# index.net
KiCad netlist of a schematic drawn in EAGLE
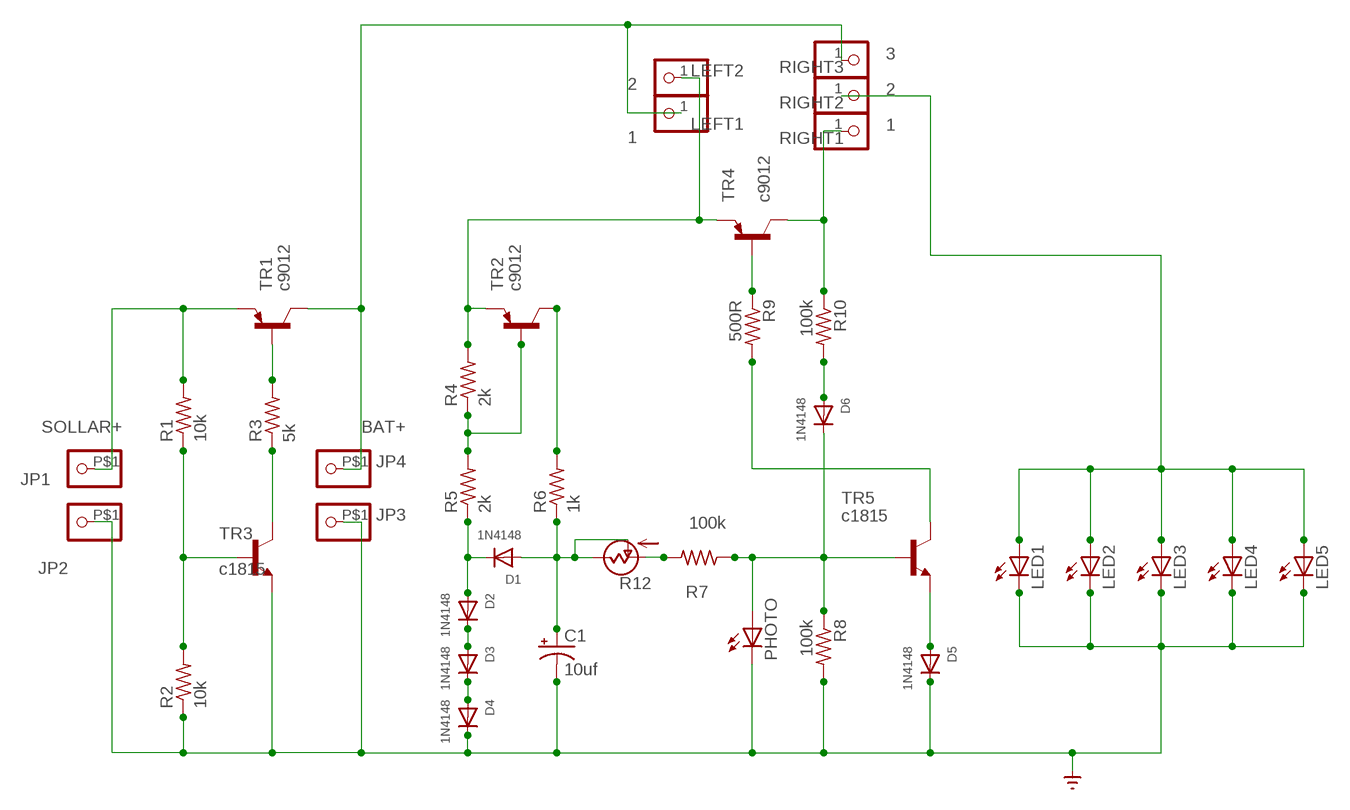
[diagram p0: schematic, sheet 1]

(export (version "E")
  (design (tool "Eeschema 10.0.6"))
  (components
    (comp (ref "C1")
      (value "10uf")
      (footprint "eagle-import:CPOL-RADIAL-10UF-25V")
      (libsource (lib "eagle-import") (part "CAP_POLPTH2"))
    )
    (comp (ref "D1")
      (value "1N4148")
      (footprint "eagle-import:DO-1N4148")
      (libsource (lib "eagle-import") (part "DIODEDO-1N4148"))
    )
    (comp (ref "D2")
      (value "1N4148")
      (footprint "eagle-import:DO-1N4148")
      (libsource (lib "eagle-import") (part "DIODEDO-1N4148"))
    )
    (comp (ref "D3")
      (value "1N4148")
      (footprint "eagle-import:DO-1N4148")
      (libsource (lib "eagle-import") (part "DIODEDO-1N4148"))
    )
    (comp (ref "D4")
      (value "1N4148")
      (footprint "eagle-import:DO-1N4148")
      (libsource (lib "eagle-import") (part "DIODEDO-1N4148"))
    )
    (comp (ref "D5")
      (value "1N4148")
      (footprint "eagle-import:DO-1N4148")
      (libsource (lib "eagle-import") (part "DIODEDO-1N4148"))
    )
    (comp (ref "D6")
      (value "1N4148")
      (footprint "eagle-import:DO-1N4148")
      (libsource (lib "eagle-import") (part "DIODEDO-1N4148"))
    )
    (comp (ref "JP1")
      (value "PINHD-1X1-BIGPOGO")
      (footprint "eagle-import:1X1-BIGPOGO")
      (libsource (lib "eagle-import") (part "PINHD-1X1-BIGPOGO"))
    )
    (comp (ref "JP2")
      (value "PINHD-1X1-BIGPOGO")
      (footprint "eagle-import:1X1-BIGPOGO")
      (libsource (lib "eagle-import") (part "PINHD-1X1-BIGPOGO"))
    )
    (comp (ref "JP3")
      (value "PINHD-1X1-BIGPOGO")
      (footprint "eagle-import:1X1-BIGPOGO")
      (libsource (lib "eagle-import") (part "PINHD-1X1-BIGPOGO"))
    )
    (comp (ref "JP4")
      (value "PINHD-1X1-BIGPOGO")
      (footprint "eagle-import:1X1-BIGPOGO")
      (libsource (lib "eagle-import") (part "PINHD-1X1-BIGPOGO"))
    )
    (comp (ref "LED1")
      (value "LED3MM")
      (footprint "eagle-import:LED3MM")
      (libsource (lib "eagle-import") (part "LED3MM"))
    )
    (comp (ref "LED2")
      (value "LED3MM")
      (footprint "eagle-import:LED3MM")
      (libsource (lib "eagle-import") (part "LED3MM"))
    )
    (comp (ref "LED3")
      (value "LED3MM")
      (footprint "eagle-import:LED3MM")
      (libsource (lib "eagle-import") (part "LED3MM"))
    )
    (comp (ref "LED4")
      (value "LED3MM")
      (footprint "eagle-import:LED3MM")
      (libsource (lib "eagle-import") (part "LED3MM"))
    )
    (comp (ref "LED5")
      (value "LED3MM")
      (footprint "eagle-import:LED3MM")
      (libsource (lib "eagle-import") (part "LED3MM"))
    )
    (comp (ref "LEFT1")
      (value "1")
      (footprint "eagle-import:1X01-CLEANBIG")
      (libsource (lib "eagle-import") (part "PINHD-1X1CB"))
    )
    (comp (ref "LEFT2")
      (value "2")
      (footprint "eagle-import:1X01-CLEANBIG")
      (libsource (lib "eagle-import") (part "PINHD-1X1CB"))
    )
    (comp (ref "PHOTO")
      (value "LED3MM")
      (footprint "eagle-import:LED3MM")
      (libsource (lib "eagle-import") (part "LED3MM"))
    )
    (comp (ref "R1")
      (value "10k")
      (footprint "eagle-import:0207_9")
      (libsource (lib "eagle-import") (part "R-US_0207/9"))
    )
    (comp (ref "R2")
      (value "10k")
      (footprint "eagle-import:0207_9")
      (libsource (lib "eagle-import") (part "R-US_0207/9"))
    )
    (comp (ref "R3")
      (value "5k")
      (footprint "eagle-import:0207_9")
      (libsource (lib "eagle-import") (part "R-US_0207/9"))
    )
    (comp (ref "R4")
      (value "2k")
      (footprint "eagle-import:0207_9")
      (libsource (lib "eagle-import") (part "R-US_0207/9"))
    )
    (comp (ref "R5")
      (value "2k")
      (footprint "eagle-import:0207_9")
      (libsource (lib "eagle-import") (part "R-US_0207/9"))
    )
    (comp (ref "R6")
      (value "1k")
      (footprint "eagle-import:0207_9")
      (libsource (lib "eagle-import") (part "R-US_0207/9"))
    )
    (comp (ref "R7")
      (value "100k")
      (footprint "eagle-import:0207_9")
      (libsource (lib "eagle-import") (part "R-US_0207/9"))
    )
    (comp (ref "R8")
      (value "100k")
      (footprint "eagle-import:0207_9")
      (libsource (lib "eagle-import") (part "R-US_0207/9"))
    )
    (comp (ref "R9")
      (value "500R")
      (footprint "eagle-import:0207_9")
      (libsource (lib "eagle-import") (part "R-US_0207/9"))
    )
    (comp (ref "R10")
      (value "100k")
      (footprint "eagle-import:0207_9")
      (libsource (lib "eagle-import") (part "R-US_0207/9"))
    )
    (comp (ref "R12")
      (value "POTTRECP10S")
      (footprint "eagle-import:ECP10S")
      (libsource (lib "eagle-import") (part "POTTRECP10S"))
    )
    (comp (ref "RIGHT1")
      (value "1")
      (footprint "eagle-import:1X01-CLEANBIG")
      (libsource (lib "eagle-import") (part "PINHD-1X1CB"))
    )
    (comp (ref "RIGHT2")
      (value "2")
      (footprint "eagle-import:1X01-CLEANBIG")
      (libsource (lib "eagle-import") (part "PINHD-1X1CB"))
    )
    (comp (ref "RIGHT3")
      (value "3")
      (footprint "eagle-import:1X01-CLEANBIG")
      (libsource (lib "eagle-import") (part "PINHD-1X1CB"))
    )
    (comp (ref "TR1")
      (value "c9012")
      (footprint "eagle-import:TO92-EBC-OVAL")
      (libsource (lib "eagle-import") (part "2N2907"))
    )
    (comp (ref "TR2")
      (value "c9012")
      (footprint "eagle-import:TO92-EBC-OVAL")
      (libsource (lib "eagle-import") (part "2N2907"))
    )
    (comp (ref "TR3")
      (value "c1815")
      (footprint "eagle-import:TO92-ECB")
      (libsource (lib "eagle-import") (part "-NPN-TO92-ECBBC639"))
    )
    (comp (ref "TR4")
      (value "c9012")
      (footprint "eagle-import:TO92-EBC-OVAL")
      (libsource (lib "eagle-import") (part "2N2907"))
    )
    (comp (ref "TR5")
      (value "c1815")
      (footprint "eagle-import:TO92-ECB")
      (libsource (lib "eagle-import") (part "-NPN-TO92-ECBBC639"))
    )
  )
  (nets
    (net (code "1") (name "/BAT+") (class "Default")
      (node (ref "JP4") (pin "P$1") (pinfunction "1_P$1") (pintype "passive"))
      (node (ref "LEFT1") (pin "1") (pinfunction "1_1") (pintype "passive"))
      (node (ref "RIGHT3") (pin "1") (pinfunction "1_1") (pintype "passive"))
      (node (ref "TR1") (pin "C") (pinfunction "C_C") (pintype "passive"))
    )
    (net (code "2") (name "/SOLLAR+") (class "Default")
      (node (ref "JP1") (pin "P$1") (pinfunction "1_P$1") (pintype "passive"))
      (node (ref "R1") (pin "2") (pinfunction "2_2") (pintype "passive"))
      (node (ref "TR1") (pin "E") (pinfunction "E_E") (pintype "passive"))
    )
    (net (code "3") (name "Net-(C1-+)") (class "Default")
      (node (ref "C1") (pin "1") (pinfunction "+_1") (pintype "passive"))
      (node (ref "D1") (pin "A") (pinfunction "A_A") (pintype "passive"))
      (node (ref "R12") (pin "E") (pinfunction "VSS_E") (pintype "passive"))
      (node (ref "R12") (pin "S") (pinfunction "OUT_S") (pintype "passive"))
      (node (ref "R6") (pin "1") (pinfunction "1_1") (pintype "passive"))
    )
    (net (code "4") (name "Net-(D1-PadC)") (class "Default")
      (node (ref "D1") (pin "C") (pinfunction "C_C") (pintype "passive"))
      (node (ref "D2") (pin "A") (pinfunction "A_A") (pintype "passive"))
      (node (ref "R5") (pin "1") (pinfunction "1_1") (pintype "passive"))
    )
    (net (code "5") (name "Net-(D2-PadC)") (class "Default")
      (node (ref "D2") (pin "C") (pinfunction "C_C") (pintype "passive"))
      (node (ref "D3") (pin "A") (pinfunction "A_A") (pintype "passive"))
    )
    (net (code "6") (name "Net-(D3-PadC)") (class "Default")
      (node (ref "D3") (pin "C") (pinfunction "C_C") (pintype "passive"))
      (node (ref "D4") (pin "A") (pinfunction "A_A") (pintype "passive"))
    )
    (net (code "7") (name "Net-(D5-PadA)") (class "Default")
      (node (ref "D5") (pin "A") (pinfunction "A_A") (pintype "passive"))
      (node (ref "TR5") (pin "E") (pinfunction "E_E") (pintype "passive"))
    )
    (net (code "8") (name "Net-(D6-PadA)") (class "Default")
      (node (ref "D6") (pin "A") (pinfunction "A_A") (pintype "passive"))
      (node (ref "R10") (pin "2") (pinfunction "2_2") (pintype "passive"))
    )
    (net (code "9") (name "Net-(D6-PadC)") (class "Default")
      (node (ref "D6") (pin "C") (pinfunction "C_C") (pintype "passive"))
      (node (ref "PHOTO") (pin "A") (pinfunction "A_A") (pintype "passive"))
      (node (ref "R7") (pin "1") (pinfunction "1_1") (pintype "passive"))
      (node (ref "R8") (pin "1") (pinfunction "1_1") (pintype "passive"))
      (node (ref "TR5") (pin "B") (pinfunction "B_B") (pintype "passive"))
    )
    (net (code "10") (name "Net-(LED1-PadA)") (class "Default")
      (node (ref "LED1") (pin "A") (pinfunction "A_A") (pintype "passive"))
      (node (ref "LED2") (pin "A") (pinfunction "A_A") (pintype "passive"))
      (node (ref "LED3") (pin "A") (pinfunction "A_A") (pintype "passive"))
      (node (ref "LED4") (pin "A") (pinfunction "A_A") (pintype "passive"))
      (node (ref "LED5") (pin "A") (pinfunction "A_A") (pintype "passive"))
      (node (ref "RIGHT2") (pin "1") (pinfunction "1_1") (pintype "passive"))
    )
    (net (code "11") (name "Net-(LEFT2-Pad1)") (class "Default")
      (node (ref "LEFT2") (pin "1") (pinfunction "1_1") (pintype "passive"))
      (node (ref "R4") (pin "2") (pinfunction "2_2") (pintype "passive"))
      (node (ref "TR2") (pin "E") (pinfunction "E_E") (pintype "passive"))
      (node (ref "TR4") (pin "E") (pinfunction "E_E") (pintype "passive"))
    )
    (net (code "12") (name "Net-(R1-Pad1)") (class "Default")
      (node (ref "R1") (pin "1") (pinfunction "1_1") (pintype "passive"))
      (node (ref "R2") (pin "2") (pinfunction "2_2") (pintype "passive"))
      (node (ref "TR3") (pin "B") (pinfunction "B_B") (pintype "passive"))
    )
    (net (code "13") (name "Net-(R3-Pad1)") (class "Default")
      (node (ref "R3") (pin "1") (pinfunction "1_1") (pintype "passive"))
      (node (ref "TR3") (pin "C") (pinfunction "C_C") (pintype "passive"))
    )
    (net (code "14") (name "Net-(R3-Pad2)") (class "Default")
      (node (ref "R3") (pin "2") (pinfunction "2_2") (pintype "passive"))
      (node (ref "TR1") (pin "B") (pinfunction "B_B") (pintype "passive"))
    )
    (net (code "15") (name "Net-(R4-Pad1)") (class "Default")
      (node (ref "R4") (pin "1") (pinfunction "1_1") (pintype "passive"))
      (node (ref "R5") (pin "2") (pinfunction "2_2") (pintype "passive"))
      (node (ref "TR2") (pin "B") (pinfunction "B_B") (pintype "passive"))
    )
    (net (code "16") (name "Net-(R6-Pad2)") (class "Default")
      (node (ref "R6") (pin "2") (pinfunction "2_2") (pintype "passive"))
      (node (ref "TR2") (pin "C") (pinfunction "C_C") (pintype "passive"))
    )
    (net (code "17") (name "Net-(R9-Pad1)") (class "Default")
      (node (ref "R9") (pin "1") (pinfunction "1_1") (pintype "passive"))
      (node (ref "TR4") (pin "B") (pinfunction "B_B") (pintype "passive"))
    )
    (net (code "18") (name "Net-(R9-Pad2)") (class "Default")
      (node (ref "R9") (pin "2") (pinfunction "2_2") (pintype "passive"))
      (node (ref "TR5") (pin "C") (pinfunction "C_C") (pintype "passive"))
    )
    (net (code "19") (name "Net-(R10-Pad1)") (class "Default")
      (node (ref "R10") (pin "1") (pinfunction "1_1") (pintype "passive"))
      (node (ref "RIGHT1") (pin "1") (pinfunction "1_1") (pintype "passive"))
      (node (ref "TR4") (pin "C") (pinfunction "C_C") (pintype "passive"))
    )
    (net (code "20") (name "Net-(R12-VDD)") (class "Default")
      (node (ref "R12") (pin "A") (pinfunction "VDD_A") (pintype "passive"))
      (node (ref "R7") (pin "2") (pinfunction "2_2") (pintype "passive"))
    )
    (net (code "21") (name "SUPPLY0_GND_") (class "Default")
      (node (ref "C1") (pin "2") (pinfunction "-_2") (pintype "passive"))
      (node (ref "D4") (pin "C") (pinfunction "C_C") (pintype "passive"))
      (node (ref "D5") (pin "C") (pinfunction "C_C") (pintype "passive"))
      (node (ref "JP2") (pin "P$1") (pinfunction "1_P$1") (pintype "passive"))
      (node (ref "JP3") (pin "P$1") (pinfunction "1_P$1") (pintype "passive"))
      (node (ref "LED1") (pin "K") (pinfunction "C_K") (pintype "passive"))
      (node (ref "LED2") (pin "K") (pinfunction "C_K") (pintype "passive"))
      (node (ref "LED3") (pin "K") (pinfunction "C_K") (pintype "passive"))
      (node (ref "LED4") (pin "K") (pinfunction "C_K") (pintype "passive"))
      (node (ref "LED5") (pin "K") (pinfunction "C_K") (pintype "passive"))
      (node (ref "PHOTO") (pin "K") (pinfunction "C_K") (pintype "passive"))
      (node (ref "R2") (pin "1") (pinfunction "1_1") (pintype "passive"))
      (node (ref "R8") (pin "2") (pinfunction "2_2") (pintype "passive"))
      (node (ref "TR3") (pin "E") (pinfunction "E_E") (pintype "passive"))
    )
  )
)
